# Smartwatch-BASIC-BOTTOM.net
KiCad netlist of a schematic drawn in EAGLE
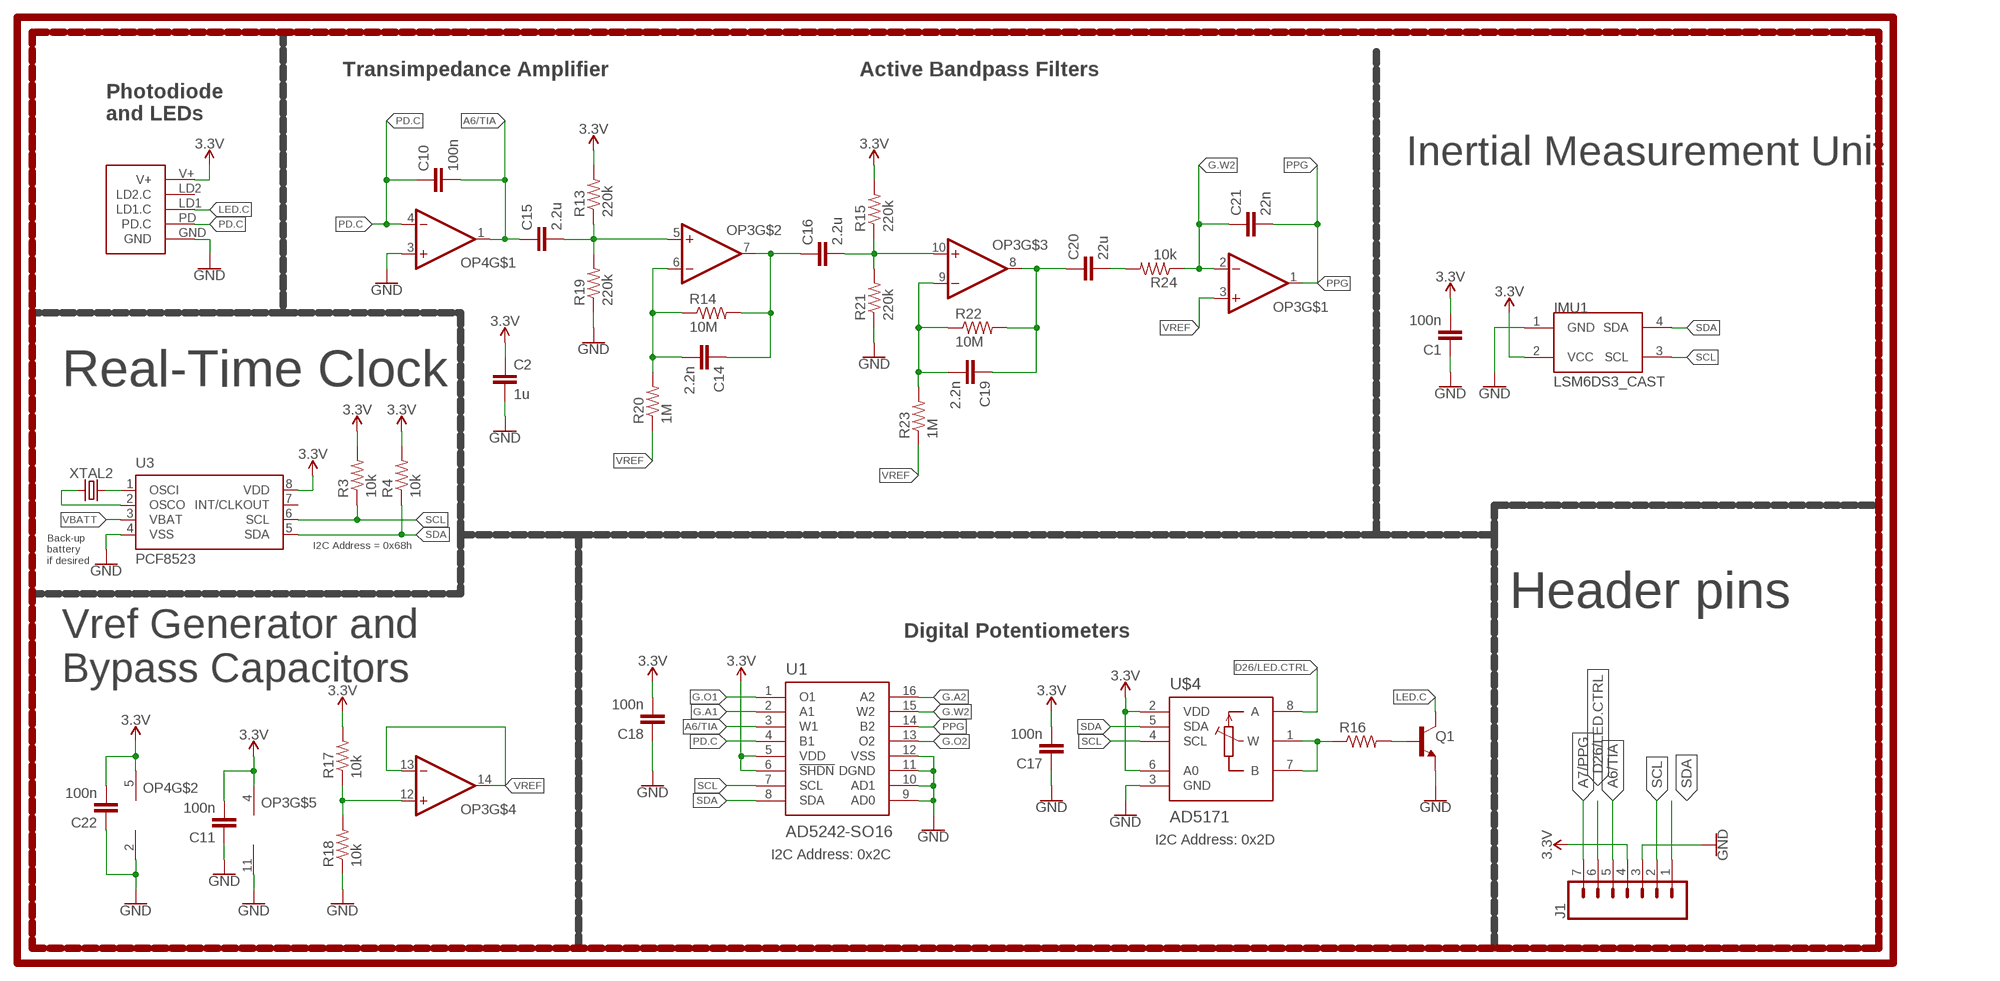
[diagram p0: schematic, sheet 1]

(export (version "E")
  (design (tool "Eeschema 10.0.6"))
  (components
    (comp (ref "C1")
      (value "100n")
      (footprint "eagle-import:C0603")
      (libsource (lib "eagle-import") (part "CAPACITOR0603"))
    )
    (comp (ref "C2")
      (value "1u")
      (footprint "eagle-import:C0603")
      (libsource (lib "eagle-import") (part "CAPACITOR0603"))
    )
    (comp (ref "C10")
      (value "100n")
      (footprint "eagle-import:C0603")
      (libsource (lib "eagle-import") (part "CAPACITOR0603"))
    )
    (comp (ref "C11")
      (value "100n")
      (footprint "eagle-import:C0603")
      (libsource (lib "eagle-import") (part "CAPACITOR0603"))
    )
    (comp (ref "C14")
      (value "2.2n")
      (footprint "eagle-import:C0603")
      (libsource (lib "eagle-import") (part "CAPACITOR0603"))
    )
    (comp (ref "C15")
      (value "2.2u")
      (footprint "eagle-import:C0603")
      (libsource (lib "eagle-import") (part "CAPACITOR0603"))
    )
    (comp (ref "C16")
      (value "2.2u")
      (footprint "eagle-import:C0603")
      (libsource (lib "eagle-import") (part "CAPACITOR0603"))
    )
    (comp (ref "C17")
      (value "100n")
      (footprint "eagle-import:C0603")
      (libsource (lib "eagle-import") (part "CAPACITOR0603"))
    )
    (comp (ref "C18")
      (value "100n")
      (footprint "eagle-import:C0603")
      (libsource (lib "eagle-import") (part "CAPACITOR0603"))
    )
    (comp (ref "C19")
      (value "2.2n")
      (footprint "eagle-import:C0603")
      (libsource (lib "eagle-import") (part "CAPACITOR0603"))
    )
    (comp (ref "C20")
      (value "22u")
      (footprint "eagle-import:C0603")
      (libsource (lib "eagle-import") (part "CAPACITOR0603"))
    )
    (comp (ref "C21")
      (value "22n")
      (footprint "eagle-import:C0603")
      (libsource (lib "eagle-import") (part "CAPACITOR0603"))
    )
    (comp (ref "C22")
      (value "100n")
      (footprint "eagle-import:C0603")
      (libsource (lib "eagle-import") (part "CAPACITOR0603"))
    )
    (comp (ref "IMU1")
      (value "LSM6DS3_CAST")
      (footprint "eagle-import:LSM6DS3_CAST")
      (libsource (lib "eagle-import") (part "LSM6DS3_CAST"))
    )
    (comp (ref "J1")
      (value "CONN_07-1.27MM")
      (footprint "eagle-import:1X07_1.27MM")
      (libsource (lib "eagle-import") (part "CONN_07-1.27MM"))
    )
    (comp (ref "OP3")
      (value "OP-QUAD-SO14")
      (footprint "eagle-import:SO14")
      (libsource (lib "eagle-import") (part "OP-QUAD-SO14"))
    )
    (comp (ref "OP4")
      (value "OP-SINGLEOT")
      (footprint "eagle-import:SOT23-5")
      (libsource (lib "eagle-import") (part "OP-SINGLEOT"))
    )
    (comp (ref "Q1")
      (value "NPN-GENERIC")
      (footprint "eagle-import:SOT23-3")
      (libsource (lib "eagle-import") (part "NPN-GENERIC"))
    )
    (comp (ref "R3")
      (value "10k")
      (footprint "eagle-import:R0603")
      (libsource (lib "eagle-import") (part "RESISTOR0603"))
    )
    (comp (ref "R4")
      (value "10k")
      (footprint "eagle-import:R0603")
      (libsource (lib "eagle-import") (part "RESISTOR0603"))
    )
    (comp (ref "R13")
      (value "220k")
      (footprint "eagle-import:R0603")
      (libsource (lib "eagle-import") (part "RESISTOR0603"))
    )
    (comp (ref "R14")
      (value "10M")
      (footprint "eagle-import:R0603")
      (libsource (lib "eagle-import") (part "RESISTOR0603"))
    )
    (comp (ref "R15")
      (value "220k")
      (footprint "eagle-import:R0603")
      (libsource (lib "eagle-import") (part "RESISTOR0603"))
    )
    (comp (ref "R16")
      (value "RESISTOR0603")
      (footprint "eagle-import:R0603")
      (libsource (lib "eagle-import") (part "RESISTOR0603"))
    )
    (comp (ref "R17")
      (value "10k")
      (footprint "eagle-import:R0402")
      (libsource (lib "eagle-import") (part "RESISTOR0402"))
    )
    (comp (ref "R18")
      (value "10k")
      (footprint "eagle-import:R0402")
      (libsource (lib "eagle-import") (part "RESISTOR0402"))
    )
    (comp (ref "R19")
      (value "220k")
      (footprint "eagle-import:R0603")
      (libsource (lib "eagle-import") (part "RESISTOR0603"))
    )
    (comp (ref "R20")
      (value "1M")
      (footprint "eagle-import:R0603")
      (libsource (lib "eagle-import") (part "RESISTOR0603"))
    )
    (comp (ref "R21")
      (value "220k")
      (footprint "eagle-import:R0603")
      (libsource (lib "eagle-import") (part "RESISTOR0603"))
    )
    (comp (ref "R22")
      (value "10M")
      (footprint "eagle-import:R0603")
      (libsource (lib "eagle-import") (part "RESISTOR0603"))
    )
    (comp (ref "R23")
      (value "1M")
      (footprint "eagle-import:R0603")
      (libsource (lib "eagle-import") (part "RESISTOR0603"))
    )
    (comp (ref "R24")
      (value "10k")
      (footprint "eagle-import:R0603")
      (libsource (lib "eagle-import") (part "RESISTOR0603"))
    )
    (comp (ref "U$3")
      (value "PPG.MODULE.2")
      (footprint "eagle-import:PPG.MODULE.2")
      (libsource (lib "eagle-import") (part "PPG.MODULE.2"))
    )
    (comp (ref "U$4")
      (value "AD5171")
      (footprint "eagle-import:SOT-23-8")
      (libsource (lib "eagle-import") (part "AD5171"))
    )
    (comp (ref "U1")
      (value "AD5242-SO16")
      (footprint "eagle-import:SO16")
      (libsource (lib "eagle-import") (part "AD5242-SO16"))
    )
    (comp (ref "U3")
      (value "PCF8523")
      (footprint "eagle-import:SO8")
      (libsource (lib "eagle-import") (part "PCF8523"))
    )
    (comp (ref "XTAL2")
      (value "32.7680kHz")
      (footprint "eagle-import:2-SMD.NOLEAD.2.0MMTO1.2MM")
      (fields (field (name "FREQ") "32.7680KHZ"))
      (libsource (lib "eagle-import") (part "CRYSTALECS-.327-12.5-12-C-TR"))
    )
  )
  (nets
    (net (code "1") (name "3.3V") (class "Default")
      (node (ref "C1") (pin "2") (pinfunction "2_2") (pintype "passive"))
      (node (ref "C11") (pin "2") (pinfunction "2_2") (pintype "passive"))
      (node (ref "C17") (pin "2") (pinfunction "2_2") (pintype "passive"))
      (node (ref "C18") (pin "2") (pinfunction "2_2") (pintype "passive"))
      (node (ref "C2") (pin "1") (pinfunction "1_1") (pintype "passive"))
      (node (ref "C22") (pin "2") (pinfunction "2_2") (pintype "passive"))
      (node (ref "IMU1") (pin "2") (pinfunction "VCC_2") (pintype "bidirectional"))
      (node (ref "J1") (pin "4") (pinfunction "4_4") (pintype "passive"))
      (node (ref "OP3") (pin "4") (pinfunction "V+_4") (pintype "power_in"))
      (node (ref "OP4") (pin "5") (pinfunction "V+_5") (pintype "power_in"))
      (node (ref "R13") (pin "2") (pinfunction "2_2") (pintype "passive"))
      (node (ref "R15") (pin "2") (pinfunction "2_2") (pintype "passive"))
      (node (ref "R17") (pin "2") (pinfunction "2_2") (pintype "passive"))
      (node (ref "R3") (pin "2") (pinfunction "2_2") (pintype "passive"))
      (node (ref "R4") (pin "2") (pinfunction "2_2") (pintype "passive"))
      (node (ref "U$3") (pin "V+") (pinfunction "V+_V+") (pintype "bidirectional"))
      (node (ref "U$4") (pin "2") (pinfunction "VDD_2") (pintype "bidirectional"))
      (node (ref "U$4") (pin "6") (pinfunction "A0_6") (pintype "bidirectional"))
      (node (ref "U1") (pin "5") (pinfunction "VDD_5") (pintype "bidirectional"))
      (node (ref "U1") (pin "6") (pinfunction "~{SHDN}_6") (pintype "bidirectional"))
      (node (ref "U3") (pin "8") (pinfunction "VDD_8") (pintype "power_in"))
    )
    (net (code "2") (name "A6{slash}TIA") (class "Default")
      (node (ref "C10") (pin "2") (pinfunction "2_2") (pintype "passive"))
      (node (ref "C15") (pin "1") (pinfunction "1_1") (pintype "passive"))
      (node (ref "J1") (pin "5") (pinfunction "5_5") (pintype "passive"))
      (node (ref "OP4") (pin "1") (pinfunction "OUT_1") (pintype "output"))
      (node (ref "U1") (pin "3") (pinfunction "W1_3") (pintype "bidirectional"))
    )
    (net (code "3") (name "A7{slash}PPG") (class "Default")
      (node (ref "J1") (pin "7") (pinfunction "7_7") (pintype "passive"))
    )
    (net (code "4") (name "D26{slash}LED.CTRL") (class "Default")
      (node (ref "J1") (pin "6") (pinfunction "6_6") (pintype "passive"))
      (node (ref "U$4") (pin "8") (pinfunction "A_8") (pintype "bidirectional"))
    )
    (net (code "5") (name "G.A1") (class "Default")
      (node (ref "U1") (pin "2") (pinfunction "A1_2") (pintype "bidirectional"))
    )
    (net (code "6") (name "G.A2") (class "Default")
      (node (ref "U1") (pin "16") (pinfunction "A2_16") (pintype "bidirectional"))
    )
    (net (code "7") (name "G.O1") (class "Default")
      (node (ref "U1") (pin "1") (pinfunction "O1_1") (pintype "bidirectional"))
    )
    (net (code "8") (name "G.O2") (class "Default")
      (node (ref "U1") (pin "13") (pinfunction "O2_13") (pintype "bidirectional"))
    )
    (net (code "9") (name "G.W2") (class "Default")
      (node (ref "C21") (pin "1") (pinfunction "1_1") (pintype "passive"))
      (node (ref "OP3") (pin "2") (pinfunction "-IN_2") (pintype "input"))
      (node (ref "R24") (pin "1") (pinfunction "1_1") (pintype "passive"))
      (node (ref "U1") (pin "15") (pinfunction "W2_15") (pintype "bidirectional"))
    )
    (net (code "10") (name "GND") (class "Default")
      (node (ref "C1") (pin "1") (pinfunction "1_1") (pintype "passive"))
      (node (ref "C11") (pin "1") (pinfunction "1_1") (pintype "passive"))
      (node (ref "C17") (pin "1") (pinfunction "1_1") (pintype "passive"))
      (node (ref "C18") (pin "1") (pinfunction "1_1") (pintype "passive"))
      (node (ref "C2") (pin "2") (pinfunction "2_2") (pintype "passive"))
      (node (ref "C22") (pin "1") (pinfunction "1_1") (pintype "passive"))
      (node (ref "IMU1") (pin "1") (pinfunction "GND_1") (pintype "bidirectional"))
      (node (ref "J1") (pin "3") (pinfunction "3_3") (pintype "passive"))
      (node (ref "OP3") (pin "11") (pinfunction "V-_11") (pintype "power_in"))
      (node (ref "OP4") (pin "2") (pinfunction "V-_2") (pintype "power_in"))
      (node (ref "OP4") (pin "3") (pinfunction "+IN_3") (pintype "input"))
      (node (ref "Q1") (pin "2") (pinfunction "E_2") (pintype "passive"))
      (node (ref "R18") (pin "1") (pinfunction "1_1") (pintype "passive"))
      (node (ref "R19") (pin "1") (pinfunction "1_1") (pintype "passive"))
      (node (ref "R21") (pin "1") (pinfunction "1_1") (pintype "passive"))
      (node (ref "U$3") (pin "GND") (pinfunction "GND_GND") (pintype "bidirectional"))
      (node (ref "U$4") (pin "3") (pinfunction "GND_3") (pintype "bidirectional"))
      (node (ref "U1") (pin "10") (pinfunction "AD1_10") (pintype "bidirectional"))
      (node (ref "U1") (pin "11") (pinfunction "DGND_11") (pintype "bidirectional"))
      (node (ref "U1") (pin "12") (pinfunction "VSS_12") (pintype "bidirectional"))
      (node (ref "U1") (pin "9") (pinfunction "AD0_9") (pintype "bidirectional"))
      (node (ref "U3") (pin "4") (pinfunction "VSS_4") (pintype "power_in"))
    )
    (net (code "11") (name "LED.C") (class "Default")
      (node (ref "Q1") (pin "3") (pinfunction "C_3") (pintype "passive"))
      (node (ref "U$3") (pin "LD1") (pinfunction "LD1.C_LD1") (pintype "bidirectional"))
    )
    (net (code "12") (name "Net-(C20-Pad2)") (class "Default")
      (node (ref "C20") (pin "2") (pinfunction "2_2") (pintype "passive"))
      (node (ref "R24") (pin "2") (pinfunction "2_2") (pintype "passive"))
    )
    (net (code "13") (name "Net-(OP3B-+IN)") (class "Default")
      (node (ref "C15") (pin "2") (pinfunction "2_2") (pintype "passive"))
      (node (ref "OP3") (pin "5") (pinfunction "+IN_5") (pintype "input"))
      (node (ref "R13") (pin "1") (pinfunction "1_1") (pintype "passive"))
      (node (ref "R19") (pin "2") (pinfunction "2_2") (pintype "passive"))
    )
    (net (code "14") (name "Net-(OP3B--IN)") (class "Default")
      (node (ref "C14") (pin "2") (pinfunction "2_2") (pintype "passive"))
      (node (ref "OP3") (pin "6") (pinfunction "-IN_6") (pintype "input"))
      (node (ref "R14") (pin "1") (pinfunction "1_1") (pintype "passive"))
      (node (ref "R20") (pin "2") (pinfunction "2_2") (pintype "passive"))
    )
    (net (code "15") (name "Net-(OP3B-OUT)") (class "Default")
      (node (ref "C14") (pin "1") (pinfunction "1_1") (pintype "passive"))
      (node (ref "C16") (pin "1") (pinfunction "1_1") (pintype "passive"))
      (node (ref "OP3") (pin "7") (pinfunction "OUT_7") (pintype "output"))
      (node (ref "R14") (pin "2") (pinfunction "2_2") (pintype "passive"))
    )
    (net (code "16") (name "Net-(OP3C-+IN)") (class "Default")
      (node (ref "C16") (pin "2") (pinfunction "2_2") (pintype "passive"))
      (node (ref "OP3") (pin "10") (pinfunction "+IN_10") (pintype "input"))
      (node (ref "R15") (pin "1") (pinfunction "1_1") (pintype "passive"))
      (node (ref "R21") (pin "2") (pinfunction "2_2") (pintype "passive"))
    )
    (net (code "17") (name "Net-(OP3C--IN)") (class "Default")
      (node (ref "C19") (pin "2") (pinfunction "2_2") (pintype "passive"))
      (node (ref "OP3") (pin "9") (pinfunction "-IN_9") (pintype "input"))
      (node (ref "R22") (pin "1") (pinfunction "1_1") (pintype "passive"))
      (node (ref "R23") (pin "2") (pinfunction "2_2") (pintype "passive"))
    )
    (net (code "18") (name "Net-(OP3C-OUT)") (class "Default")
      (node (ref "C19") (pin "1") (pinfunction "1_1") (pintype "passive"))
      (node (ref "C20") (pin "1") (pinfunction "1_1") (pintype "passive"))
      (node (ref "OP3") (pin "8") (pinfunction "OUT_8") (pintype "output"))
      (node (ref "R22") (pin "2") (pinfunction "2_2") (pintype "passive"))
    )
    (net (code "19") (name "Net-(OP3D-+IN)") (class "Default")
      (node (ref "OP3") (pin "12") (pinfunction "+IN_12") (pintype "input"))
      (node (ref "R17") (pin "1") (pinfunction "1_1") (pintype "passive"))
      (node (ref "R18") (pin "2") (pinfunction "2_2") (pintype "passive"))
    )
    (net (code "20") (name "Net-(Q1-B)") (class "Default")
      (node (ref "Q1") (pin "1") (pinfunction "B_1") (pintype "passive"))
      (node (ref "R16") (pin "2") (pinfunction "2_2") (pintype "passive"))
    )
    (net (code "21") (name "Net-(U$4-B)") (class "Default")
      (node (ref "R16") (pin "1") (pinfunction "1_1") (pintype "passive"))
      (node (ref "U$4") (pin "1") (pinfunction "W_1") (pintype "bidirectional"))
      (node (ref "U$4") (pin "7") (pinfunction "B_7") (pintype "bidirectional"))
    )
    (net (code "22") (name "Net-(U3-OSCI)") (class "Default")
      (node (ref "U3") (pin "1") (pinfunction "OSCI_1") (pintype "bidirectional"))
      (node (ref "XTAL2") (pin "P$2") (pinfunction "2_P$2") (pintype "passive"))
    )
    (net (code "23") (name "Net-(U3-OSCO)") (class "Default")
      (node (ref "U3") (pin "2") (pinfunction "OSCO_2") (pintype "bidirectional"))
      (node (ref "XTAL2") (pin "P$1") (pinfunction "1_P$1") (pintype "passive"))
    )
    (net (code "24") (name "PD.C") (class "Default")
      (node (ref "C10") (pin "1") (pinfunction "1_1") (pintype "passive"))
      (node (ref "OP4") (pin "4") (pinfunction "-IN_4") (pintype "input"))
      (node (ref "U$3") (pin "PD") (pinfunction "PD.C_PD") (pintype "bidirectional"))
      (node (ref "U1") (pin "4") (pinfunction "B1_4") (pintype "bidirectional"))
    )
    (net (code "25") (name "PPG") (class "Default")
      (node (ref "C21") (pin "2") (pinfunction "2_2") (pintype "passive"))
      (node (ref "OP3") (pin "1") (pinfunction "OUT_1") (pintype "output"))
      (node (ref "U1") (pin "14") (pinfunction "B2_14") (pintype "bidirectional"))
    )
    (net (code "26") (name "SCL") (class "Default")
      (node (ref "IMU1") (pin "3") (pinfunction "SCL_3") (pintype "bidirectional"))
      (node (ref "J1") (pin "2") (pinfunction "2_2") (pintype "passive"))
      (node (ref "R3") (pin "1") (pinfunction "1_1") (pintype "passive"))
      (node (ref "U$4") (pin "4") (pinfunction "SCL_4") (pintype "bidirectional"))
      (node (ref "U1") (pin "7") (pinfunction "SCL_7") (pintype "bidirectional"))
      (node (ref "U3") (pin "6") (pinfunction "SCL_6") (pintype "bidirectional"))
    )
    (net (code "27") (name "SDA") (class "Default")
      (node (ref "IMU1") (pin "4") (pinfunction "SDA_4") (pintype "bidirectional"))
      (node (ref "J1") (pin "1") (pinfunction "1_1") (pintype "passive"))
      (node (ref "R4") (pin "1") (pinfunction "1_1") (pintype "passive"))
      (node (ref "U$4") (pin "5") (pinfunction "SDA_5") (pintype "bidirectional"))
      (node (ref "U1") (pin "8") (pinfunction "SDA_8") (pintype "bidirectional"))
      (node (ref "U3") (pin "5") (pinfunction "SDA_5") (pintype "bidirectional"))
    )
    (net (code "28") (name "VBATT") (class "Default")
      (node (ref "U3") (pin "3") (pinfunction "VBAT_3") (pintype "power_in"))
    )
    (net (code "29") (name "VREF") (class "Default")
      (node (ref "OP3") (pin "13") (pinfunction "-IN_13") (pintype "input"))
      (node (ref "OP3") (pin "14") (pinfunction "OUT_14") (pintype "output"))
      (node (ref "OP3") (pin "3") (pinfunction "+IN_3") (pintype "input"))
      (node (ref "R20") (pin "1") (pinfunction "1_1") (pintype "passive"))
      (node (ref "R23") (pin "1") (pinfunction "1_1") (pintype "passive"))
    )
    (net (code "30") (name "unconnected-(U$3-LD2.C-PadLD2)") (class "Default")
      (node (ref "U$3") (pin "LD2") (pinfunction "LD2.C_LD2") (pintype "bidirectional"))
    )
    (net (code "31") (name "unconnected-(U3-INT{slash}CLKOUT-Pad7)") (class "Default")
      (node (ref "U3") (pin "7") (pinfunction "INT/CLKOUT_7") (pintype "bidirectional"))
    )
  )
)
